# cv_pot.net
KiCad netlist of a schematic drawn in EAGLE
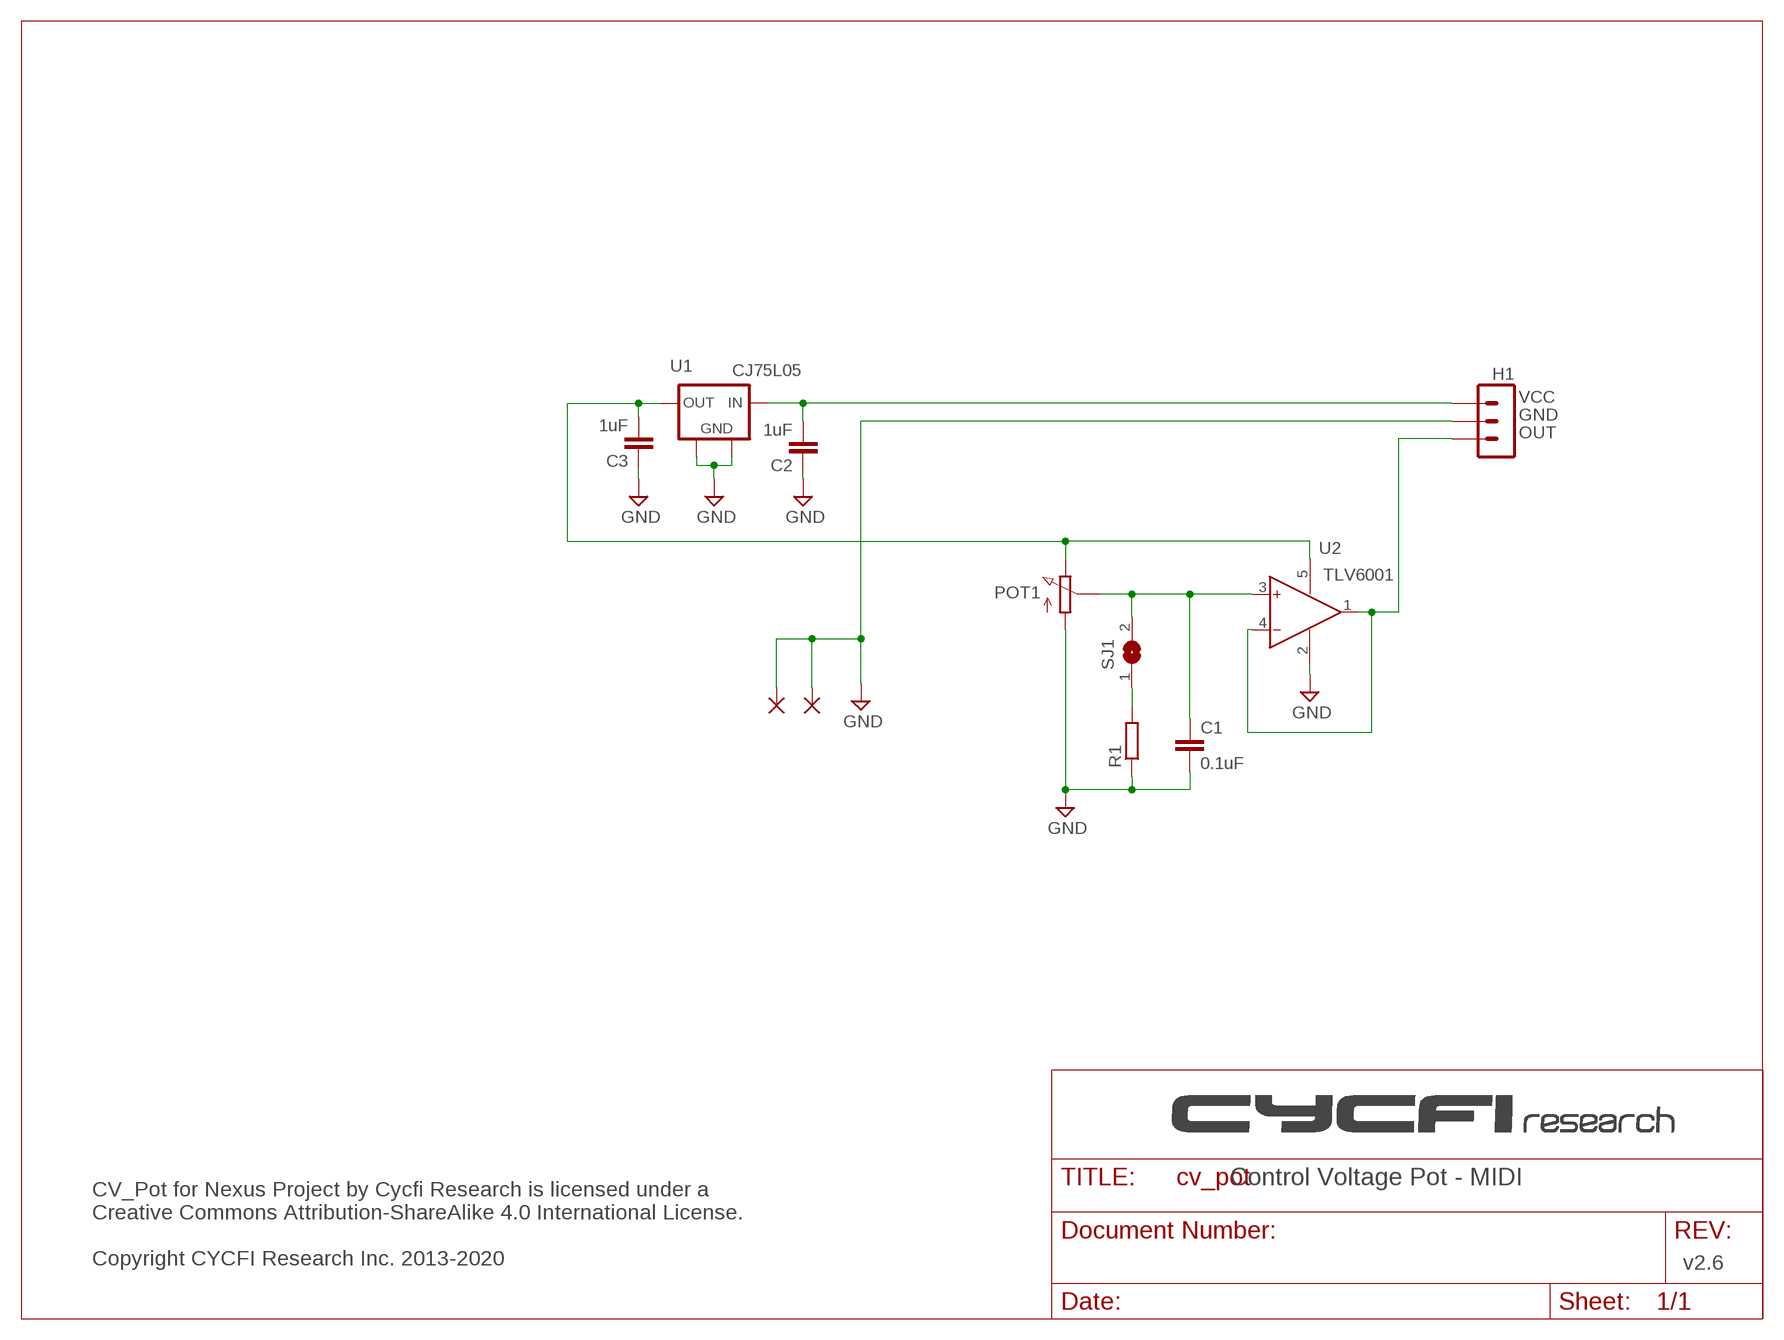
[diagram p0: schematic, sheet 1]

(export (version "E")
  (design (tool "Eeschema 10.0.6"))
  (components
    (comp (ref "C1")
      (value "0.1uF")
      (footprint "eagle-import:C0402")
      (libsource (lib "eagle-import") (part "C-EUC0402"))
    )
    (comp (ref "C2")
      (value "1uF")
      (footprint "eagle-import:C0603")
      (libsource (lib "eagle-import") (part "C-EUC0603"))
    )
    (comp (ref "C3")
      (value "1uF")
      (footprint "eagle-import:C0603")
      (libsource (lib "eagle-import") (part "C-EUC0603"))
    )
    (comp (ref "GND1")
      (value "SMD2")
      (footprint "eagle-import:SMD1,27-2,54")
      (libsource (lib "eagle-import") (part "SMD2"))
    )
    (comp (ref "GND2")
      (value "SMD2")
      (footprint "eagle-import:SMD1,27-2,54")
      (libsource (lib "eagle-import") (part "SMD2"))
    )
    (comp (ref "H1")
      (value "3PIN-SMD-2.54MM")
      (footprint "eagle-import:3P-SMD-2.54MM")
      (libsource (lib "eagle-import") (part "3PIN-SMD-2.54MM"))
    )
    (comp (ref "POT1")
      (value "25K")
      (footprint "eagle-import:POT_EU_PDB181GTR")
      (libsource (lib "eagle-import") (part "POTPDB181GTR"))
    )
    (comp (ref "R1")
      (value "R-EU_R0402")
      (footprint "eagle-import:R0402")
      (libsource (lib "eagle-import") (part "R-EU_R0402"))
    )
    (comp (ref "SJ1") (value "SJ") (footprint "eagle-import:SJ") (libsource (lib "eagle-import") (part "SJ")))
    (comp (ref "U1")
      (value "L78LXX")
      (footprint "eagle-import:SOT89")
      (libsource (lib "eagle-import") (part "L78LXX"))
    )
    (comp (ref "U2")
      (value "TLV6001")
      (footprint "eagle-import:SOT23-5")
      (libsource (lib "eagle-import") (part "TLV170"))
    )
  )
  (nets
    (net (code "1") (name "GND") (class "Default")
      (node (ref "C1") (pin "2") (pinfunction "2_2") (pintype "passive"))
      (node (ref "C2") (pin "1") (pinfunction "1_1") (pintype "passive"))
      (node (ref "C3") (pin "1") (pinfunction "1_1") (pintype "passive"))
      (node (ref "GND1") (pin "1") (pinfunction "P_1") (pintype "passive"))
      (node (ref "GND2") (pin "1") (pinfunction "P_1") (pintype "passive"))
      (node (ref "H1") (pin "P$2") (pinfunction "2_P$2") (pintype "passive"))
      (node (ref "POT1") (pin "A1") (pinfunction "1_A1") (pintype "passive"))
      (node (ref "R1") (pin "1") (pinfunction "1_1") (pintype "passive"))
      (node (ref "U1") (pin "2") (pinfunction "GND_2") (pintype "input"))
      (node (ref "U1") (pin "2@1") (pinfunction "GND1_2@1") (pintype "input"))
      (node (ref "U2") (pin "2") (pinfunction "V-_2") (pintype "power_in"))
    )
    (net (code "2") (name "Net-(H1-1)") (class "Default")
      (node (ref "H1") (pin "P$1") (pinfunction "1_P$1") (pintype "passive"))
      (node (ref "U2") (pin "1") (pinfunction "OUT_1") (pintype "output"))
      (node (ref "U2") (pin "4") (pinfunction "IN-_4") (pintype "input"))
    )
    (net (code "3") (name "Net-(H1-3)") (class "Default")
      (node (ref "C2") (pin "2") (pinfunction "2_2") (pintype "passive"))
      (node (ref "H1") (pin "P$3") (pinfunction "3_P$3") (pintype "passive"))
      (node (ref "U1") (pin "3") (pinfunction "OUT_3") (pintype "passive"))
    )
    (net (code "4") (name "Net-(POT1-2)") (class "Default")
      (node (ref "C1") (pin "1") (pinfunction "1_1") (pintype "passive"))
      (node (ref "POT1") (pin "A2") (pinfunction "2_A2") (pintype "passive"))
      (node (ref "SJ1") (pin "2") (pinfunction "2_2") (pintype "passive"))
      (node (ref "U2") (pin "3") (pinfunction "IN+_3") (pintype "input"))
    )
    (net (code "5") (name "Net-(POT1-3)") (class "Default")
      (node (ref "C3") (pin "2") (pinfunction "2_2") (pintype "passive"))
      (node (ref "POT1") (pin "A3") (pinfunction "3_A3") (pintype "passive"))
      (node (ref "U1") (pin "1") (pinfunction "IN_1") (pintype "input"))
      (node (ref "U2") (pin "5") (pinfunction "V+_5") (pintype "power_in"))
    )
    (net (code "6") (name "Net-(R1-Pad2)") (class "Default")
      (node (ref "R1") (pin "2") (pinfunction "2_2") (pintype "passive"))
      (node (ref "SJ1") (pin "1") (pinfunction "1_1") (pintype "passive"))
    )
  )
)
